# BeatLights.net
KiCad netlist of a schematic drawn in EAGLE
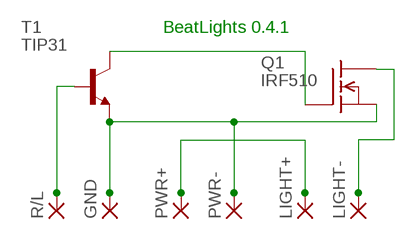
[diagram p0: schematic, sheet 1]

(export (version "E")
  (design (tool "Eeschema 10.0.6"))
  (components
    (comp (ref "GND")
      (value "1,6/0,8")
      (footprint "eagle-import:1,6_0,8")
      (libsource (lib "eagle-import") (part "1,6/0,8"))
    )
    (comp (ref "LIGHT+")
      (value "1,6/0,8")
      (footprint "eagle-import:1,6_0,8")
      (libsource (lib "eagle-import") (part "1,6/0,8"))
    )
    (comp (ref "LIGHT-")
      (value "1,6/0,8")
      (footprint "eagle-import:1,6_0,8")
      (libsource (lib "eagle-import") (part "1,6/0,8"))
    )
    (comp (ref "PWR+")
      (value "1,6/0,8")
      (footprint "eagle-import:1,6_0,8")
      (libsource (lib "eagle-import") (part "1,6/0,8"))
    )
    (comp (ref "PWR-")
      (value "1,6/0,8")
      (footprint "eagle-import:1,6_0,8")
      (libsource (lib "eagle-import") (part "1,6/0,8"))
    )
    (comp (ref "Q1")
      (value "IRF510")
      (footprint "eagle-import:TO220")
      (libsource (lib "eagle-import") (part "IRF510"))
    )
    (comp (ref "R/L")
      (value "1,6/0,8")
      (footprint "eagle-import:1,6_0,8")
      (libsource (lib "eagle-import") (part "1,6/0,8"))
    )
    (comp (ref "T1")
      (value "TIP31")
      (footprint "eagle-import:TO220")
      (libsource (lib "eagle-import") (part "TIP31"))
    )
  )
  (nets
    (net (code "1") (name "Net-(GND-P)") (class "Default")
      (node (ref "GND") (pin "1") (pinfunction "P_1") (pintype "passive"))
      (node (ref "PWR-") (pin "1") (pinfunction "P_1") (pintype "passive"))
      (node (ref "Q1") (pin "3") (pinfunction "S_3") (pintype "passive"))
      (node (ref "T1") (pin "3") (pinfunction "E_3") (pintype "passive"))
    )
    (net (code "2") (name "Net-(LIGHT+-P)") (class "Default")
      (node (ref "LIGHT+") (pin "1") (pinfunction "P_1") (pintype "passive"))
      (node (ref "PWR+") (pin "1") (pinfunction "P_1") (pintype "passive"))
    )
    (net (code "3") (name "Net-(LIGHT--P)") (class "Default")
      (node (ref "LIGHT-") (pin "1") (pinfunction "P_1") (pintype "passive"))
      (node (ref "Q1") (pin "2") (pinfunction "D_2") (pintype "passive"))
    )
    (net (code "4") (name "Net-(Q1-G)") (class "Default")
      (node (ref "Q1") (pin "1") (pinfunction "G_1") (pintype "passive"))
      (node (ref "T1") (pin "2") (pinfunction "C_2") (pintype "passive"))
    )
    (net (code "5") (name "Net-(R/L-P)") (class "Default")
      (node (ref "R/L") (pin "1") (pinfunction "P_1") (pintype "passive"))
      (node (ref "T1") (pin "1") (pinfunction "B_1") (pintype "passive"))
    )
  )
)
